# 20317.net
KiCad netlist of a schematic drawn in EAGLE
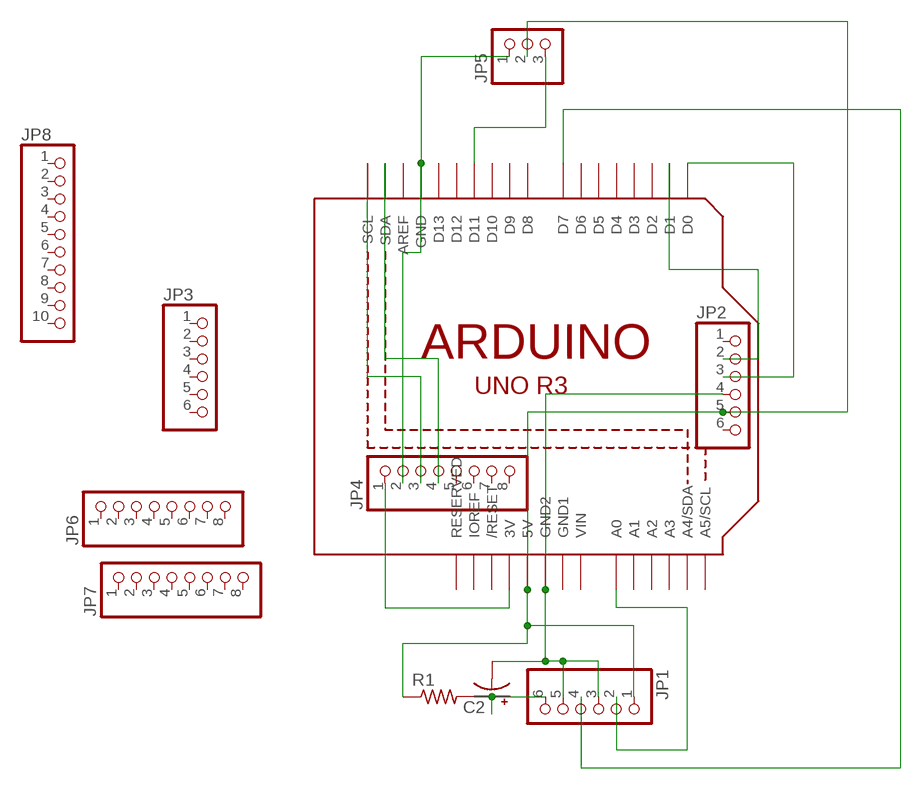
[diagram p0: schematic, sheet 1]

(export (version "E")
  (design (tool "Eeschema 10.0.6"))
  (components
    (comp (ref "C2")
      (value "CPOL-USE2.5-7")
      (footprint "eagle-import:E2,5-7")
      (libsource (lib "eagle-import") (part "CPOL-USE2.5-7"))
    )
    (comp (ref "JP1")
      (value "PINHD-1X6")
      (footprint "eagle-import:1X06")
      (libsource (lib "eagle-import") (part "PINHD-1X6"))
    )
    (comp (ref "JP2")
      (value "PINHD-1X6")
      (footprint "eagle-import:1X06")
      (libsource (lib "eagle-import") (part "PINHD-1X6"))
    )
    (comp (ref "JP3")
      (value "PINHD-1X6")
      (footprint "eagle-import:1X06")
      (libsource (lib "eagle-import") (part "PINHD-1X6"))
    )
    (comp (ref "JP4")
      (value "PINHD-1X8")
      (footprint "eagle-import:1X08")
      (libsource (lib "eagle-import") (part "PINHD-1X8"))
    )
    (comp (ref "JP5")
      (value "PINHD-1X3")
      (footprint "eagle-import:1X03")
      (libsource (lib "eagle-import") (part "PINHD-1X3"))
    )
    (comp (ref "JP6")
      (value "PINHD-1X8")
      (footprint "eagle-import:1X08")
      (libsource (lib "eagle-import") (part "PINHD-1X8"))
    )
    (comp (ref "JP7")
      (value "PINHD-1X8")
      (footprint "eagle-import:1X08")
      (libsource (lib "eagle-import") (part "PINHD-1X8"))
    )
    (comp (ref "JP8")
      (value "PINHD-1X10")
      (footprint "eagle-import:1X10")
      (libsource (lib "eagle-import") (part "PINHD-1X10"))
    )
    (comp (ref "R1")
      (value "R-US_0207/7")
      (footprint "eagle-import:0207_7")
      (libsource (lib "eagle-import") (part "R-US_0207/7"))
    )
    (comp (ref "U1")
      (value "ARDUINOR3-BPLACE")
      (footprint "eagle-import:ARDUINOR3-BPLACE")
      (libsource (lib "eagle-import") (part "ARDUINOR3-BPLACE"))
    )
  )
  (nets
    (net (code "1") (name "/GND1") (class "Default")
      (node (ref "U1") (pin "GND1") (pinfunction "GND1_GND1") (pintype "power_in"))
    )
    (net (code "2") (name "/VIN") (class "Default")
      (node (ref "U1") (pin "VIN") (pinfunction "VIN_VIN") (pintype "power_in"))
    )
    (net (code "3") (name "Net-(C2-Pad+)") (class "Default")
      (node (ref "C2") (pin "+") (pinfunction "+_+") (pintype "passive"))
      (node (ref "JP1") (pin "6") (pinfunction "6_6") (pintype "passive"))
      (node (ref "R1") (pin "2") (pinfunction "2_2") (pintype "passive"))
    )
    (net (code "4") (name "Net-(C2-Pad-)") (class "Default")
      (node (ref "C2") (pin "-") (pinfunction "-_-") (pintype "passive"))
      (node (ref "JP1") (pin "3") (pinfunction "3_3") (pintype "passive"))
      (node (ref "JP1") (pin "5") (pinfunction "5_5") (pintype "passive"))
      (node (ref "JP2") (pin "4") (pinfunction "4_4") (pintype "passive"))
      (node (ref "U1") (pin "GND2") (pinfunction "GND2_GND2") (pintype "power_in"))
    )
    (net (code "5") (name "Net-(JP1-Pad1)") (class "Default")
      (node (ref "JP1") (pin "1") (pinfunction "1_1") (pintype "passive"))
      (node (ref "JP2") (pin "5") (pinfunction "5_5") (pintype "passive"))
      (node (ref "JP5") (pin "2") (pinfunction "2_2") (pintype "passive"))
      (node (ref "R1") (pin "1") (pinfunction "1_1") (pintype "passive"))
      (node (ref "U1") (pin "5V") (pinfunction "5V_5V") (pintype "power_in"))
    )
    (net (code "6") (name "Net-(JP1-Pad2)") (class "Default")
      (node (ref "JP1") (pin "2") (pinfunction "2_2") (pintype "passive"))
      (node (ref "U1") (pin "A0") (pinfunction "A0_A0") (pintype "bidirectional"))
    )
    (net (code "7") (name "Net-(JP1-Pad4)") (class "Default")
      (node (ref "JP1") (pin "4") (pinfunction "4_4") (pintype "passive"))
      (node (ref "U1") (pin "D7") (pinfunction "D7_D7") (pintype "bidirectional"))
    )
    (net (code "8") (name "Net-(JP2-Pad2)") (class "Default")
      (node (ref "JP2") (pin "2") (pinfunction "2_2") (pintype "passive"))
      (node (ref "U1") (pin "D1") (pinfunction "D1_D1") (pintype "bidirectional"))
    )
    (net (code "9") (name "Net-(JP2-Pad3)") (class "Default")
      (node (ref "JP2") (pin "3") (pinfunction "3_3") (pintype "passive"))
      (node (ref "U1") (pin "D0") (pinfunction "D0_D0") (pintype "bidirectional"))
    )
    (net (code "10") (name "Net-(JP4-Pad1)") (class "Default")
      (node (ref "JP4") (pin "1") (pinfunction "1_1") (pintype "passive"))
      (node (ref "U1") (pin "3V") (pinfunction "3V_3V") (pintype "power_in"))
    )
    (net (code "11") (name "Net-(JP4-Pad2)") (class "Default")
      (node (ref "JP4") (pin "2") (pinfunction "2_2") (pintype "passive"))
      (node (ref "JP5") (pin "1") (pinfunction "1_1") (pintype "passive"))
      (node (ref "U1") (pin "GND") (pinfunction "GND_GND") (pintype "power_in"))
    )
    (net (code "12") (name "Net-(JP4-Pad3)") (class "Default")
      (node (ref "JP4") (pin "3") (pinfunction "3_3") (pintype "passive"))
      (node (ref "U1") (pin "SCL") (pinfunction "SCL_SCL") (pintype "bidirectional"))
    )
    (net (code "13") (name "Net-(JP4-Pad4)") (class "Default")
      (node (ref "JP4") (pin "4") (pinfunction "4_4") (pintype "passive"))
      (node (ref "U1") (pin "SDA") (pinfunction "SDA_SDA") (pintype "bidirectional"))
    )
    (net (code "14") (name "Net-(JP5-Pad3)") (class "Default")
      (node (ref "JP5") (pin "3") (pinfunction "3_3") (pintype "passive"))
      (node (ref "U1") (pin "D11") (pinfunction "D11_D11") (pintype "bidirectional"))
    )
    (net (code "15") (name "unconnected-(JP2-Pad1)") (class "Default")
      (node (ref "JP2") (pin "1") (pinfunction "1_1") (pintype "passive"))
    )
    (net (code "16") (name "unconnected-(JP2-Pad6)") (class "Default")
      (node (ref "JP2") (pin "6") (pinfunction "6_6") (pintype "passive"))
    )
    (net (code "17") (name "unconnected-(JP3-Pad1)") (class "Default")
      (node (ref "JP3") (pin "1") (pinfunction "1_1") (pintype "passive"))
    )
    (net (code "18") (name "unconnected-(JP3-Pad2)") (class "Default")
      (node (ref "JP3") (pin "2") (pinfunction "2_2") (pintype "passive"))
    )
    (net (code "19") (name "unconnected-(JP3-Pad3)") (class "Default")
      (node (ref "JP3") (pin "3") (pinfunction "3_3") (pintype "passive"))
    )
    (net (code "20") (name "unconnected-(JP3-Pad4)") (class "Default")
      (node (ref "JP3") (pin "4") (pinfunction "4_4") (pintype "passive"))
    )
    (net (code "21") (name "unconnected-(JP3-Pad5)") (class "Default")
      (node (ref "JP3") (pin "5") (pinfunction "5_5") (pintype "passive"))
    )
    (net (code "22") (name "unconnected-(JP3-Pad6)") (class "Default")
      (node (ref "JP3") (pin "6") (pinfunction "6_6") (pintype "passive"))
    )
    (net (code "23") (name "unconnected-(JP4-Pad5)") (class "Default")
      (node (ref "JP4") (pin "5") (pinfunction "5_5") (pintype "passive"))
    )
    (net (code "24") (name "unconnected-(JP4-Pad6)") (class "Default")
      (node (ref "JP4") (pin "6") (pinfunction "6_6") (pintype "passive"))
    )
    (net (code "25") (name "unconnected-(JP4-Pad7)") (class "Default")
      (node (ref "JP4") (pin "7") (pinfunction "7_7") (pintype "passive"))
    )
    (net (code "26") (name "unconnected-(JP4-Pad8)") (class "Default")
      (node (ref "JP4") (pin "8") (pinfunction "8_8") (pintype "passive"))
    )
    (net (code "27") (name "unconnected-(JP6-Pad1)") (class "Default")
      (node (ref "JP6") (pin "1") (pinfunction "1_1") (pintype "passive"))
    )
    (net (code "28") (name "unconnected-(JP6-Pad2)") (class "Default")
      (node (ref "JP6") (pin "2") (pinfunction "2_2") (pintype "passive"))
    )
    (net (code "29") (name "unconnected-(JP6-Pad3)") (class "Default")
      (node (ref "JP6") (pin "3") (pinfunction "3_3") (pintype "passive"))
    )
    (net (code "30") (name "unconnected-(JP6-Pad4)") (class "Default")
      (node (ref "JP6") (pin "4") (pinfunction "4_4") (pintype "passive"))
    )
    (net (code "31") (name "unconnected-(JP6-Pad5)") (class "Default")
      (node (ref "JP6") (pin "5") (pinfunction "5_5") (pintype "passive"))
    )
    (net (code "32") (name "unconnected-(JP6-Pad6)") (class "Default")
      (node (ref "JP6") (pin "6") (pinfunction "6_6") (pintype "passive"))
    )
    (net (code "33") (name "unconnected-(JP6-Pad7)") (class "Default")
      (node (ref "JP6") (pin "7") (pinfunction "7_7") (pintype "passive"))
    )
    (net (code "34") (name "unconnected-(JP6-Pad8)") (class "Default")
      (node (ref "JP6") (pin "8") (pinfunction "8_8") (pintype "passive"))
    )
    (net (code "35") (name "unconnected-(JP7-Pad1)") (class "Default")
      (node (ref "JP7") (pin "1") (pinfunction "1_1") (pintype "passive"))
    )
    (net (code "36") (name "unconnected-(JP7-Pad2)") (class "Default")
      (node (ref "JP7") (pin "2") (pinfunction "2_2") (pintype "passive"))
    )
    (net (code "37") (name "unconnected-(JP7-Pad3)") (class "Default")
      (node (ref "JP7") (pin "3") (pinfunction "3_3") (pintype "passive"))
    )
    (net (code "38") (name "unconnected-(JP7-Pad4)") (class "Default")
      (node (ref "JP7") (pin "4") (pinfunction "4_4") (pintype "passive"))
    )
    (net (code "39") (name "unconnected-(JP7-Pad5)") (class "Default")
      (node (ref "JP7") (pin "5") (pinfunction "5_5") (pintype "passive"))
    )
    (net (code "40") (name "unconnected-(JP7-Pad6)") (class "Default")
      (node (ref "JP7") (pin "6") (pinfunction "6_6") (pintype "passive"))
    )
    (net (code "41") (name "unconnected-(JP7-Pad7)") (class "Default")
      (node (ref "JP7") (pin "7") (pinfunction "7_7") (pintype "passive"))
    )
    (net (code "42") (name "unconnected-(JP7-Pad8)") (class "Default")
      (node (ref "JP7") (pin "8") (pinfunction "8_8") (pintype "passive"))
    )
    (net (code "43") (name "unconnected-(JP8-Pad1)") (class "Default")
      (node (ref "JP8") (pin "1") (pinfunction "1_1") (pintype "passive"))
    )
    (net (code "44") (name "unconnected-(JP8-Pad2)") (class "Default")
      (node (ref "JP8") (pin "2") (pinfunction "2_2") (pintype "passive"))
    )
    (net (code "45") (name "unconnected-(JP8-Pad3)") (class "Default")
      (node (ref "JP8") (pin "3") (pinfunction "3_3") (pintype "passive"))
    )
    (net (code "46") (name "unconnected-(JP8-Pad4)") (class "Default")
      (node (ref "JP8") (pin "4") (pinfunction "4_4") (pintype "passive"))
    )
    (net (code "47") (name "unconnected-(JP8-Pad5)") (class "Default")
      (node (ref "JP8") (pin "5") (pinfunction "5_5") (pintype "passive"))
    )
    (net (code "48") (name "unconnected-(JP8-Pad6)") (class "Default")
      (node (ref "JP8") (pin "6") (pinfunction "6_6") (pintype "passive"))
    )
    (net (code "49") (name "unconnected-(JP8-Pad7)") (class "Default")
      (node (ref "JP8") (pin "7") (pinfunction "7_7") (pintype "passive"))
    )
    (net (code "50") (name "unconnected-(JP8-Pad8)") (class "Default")
      (node (ref "JP8") (pin "8") (pinfunction "8_8") (pintype "passive"))
    )
    (net (code "51") (name "unconnected-(JP8-Pad9)") (class "Default")
      (node (ref "JP8") (pin "9") (pinfunction "9_9") (pintype "passive"))
    )
    (net (code "52") (name "unconnected-(JP8-Pad10)") (class "Default")
      (node (ref "JP8") (pin "10") (pinfunction "10_10") (pintype "passive"))
    )
    (net (code "53") (name "unconnected-(U1-A4{slash}SDA-PadA4)") (class "Default")
      (node (ref "U1") (pin "A4") (pinfunction "A4/SDA_A4") (pintype "bidirectional"))
    )
    (net (code "54") (name "unconnected-(U1-A5{slash}SCL-PadA5)") (class "Default")
      (node (ref "U1") (pin "A5") (pinfunction "A5/SCL_A5") (pintype "bidirectional"))
    )
    (net (code "55") (name "unconnected-(U1-PadA1)") (class "Default")
      (node (ref "U1") (pin "A1") (pinfunction "A1_A1") (pintype "bidirectional"))
    )
    (net (code "56") (name "unconnected-(U1-PadA2)") (class "Default")
      (node (ref "U1") (pin "A2") (pinfunction "A2_A2") (pintype "bidirectional"))
    )
    (net (code "57") (name "unconnected-(U1-PadA3)") (class "Default")
      (node (ref "U1") (pin "A3") (pinfunction "A3_A3") (pintype "bidirectional"))
    )
    (net (code "58") (name "unconnected-(U1-PadAREF)") (class "Default")
      (node (ref "U1") (pin "AREF") (pinfunction "AREF_AREF") (pintype "bidirectional"))
    )
    (net (code "59") (name "unconnected-(U1-PadD2)") (class "Default")
      (node (ref "U1") (pin "D2") (pinfunction "D2_D2") (pintype "bidirectional"))
    )
    (net (code "60") (name "unconnected-(U1-PadD3)") (class "Default")
      (node (ref "U1") (pin "D3") (pinfunction "D3_D3") (pintype "bidirectional"))
    )
    (net (code "61") (name "unconnected-(U1-PadD4)") (class "Default")
      (node (ref "U1") (pin "D4") (pinfunction "D4_D4") (pintype "bidirectional"))
    )
    (net (code "62") (name "unconnected-(U1-PadD5)") (class "Default")
      (node (ref "U1") (pin "D5") (pinfunction "D5_D5") (pintype "bidirectional"))
    )
    (net (code "63") (name "unconnected-(U1-PadD6)") (class "Default")
      (node (ref "U1") (pin "D6") (pinfunction "D6_D6") (pintype "bidirectional"))
    )
    (net (code "64") (name "unconnected-(U1-PadD8)") (class "Default")
      (node (ref "U1") (pin "D8") (pinfunction "D8_D8") (pintype "bidirectional"))
    )
    (net (code "65") (name "unconnected-(U1-PadD9)") (class "Default")
      (node (ref "U1") (pin "D9") (pinfunction "D9_D9") (pintype "bidirectional"))
    )
    (net (code "66") (name "unconnected-(U1-PadD10)") (class "Default")
      (node (ref "U1") (pin "D10") (pinfunction "D10_D10") (pintype "bidirectional"))
    )
    (net (code "67") (name "unconnected-(U1-PadD12)") (class "Default")
      (node (ref "U1") (pin "D12") (pinfunction "D12_D12") (pintype "bidirectional"))
    )
    (net (code "68") (name "unconnected-(U1-PadD13)") (class "Default")
      (node (ref "U1") (pin "D13") (pinfunction "D13_D13") (pintype "bidirectional"))
    )
    (net (code "69") (name "unconnected-(U1-PadIOREF)") (class "Default")
      (node (ref "U1") (pin "IOREF") (pinfunction "IOREF_IOREF") (pintype "output"))
    )
    (net (code "70") (name "unconnected-(U1-PadRESERVED)") (class "Default")
      (node (ref "U1") (pin "RESERVED") (pinfunction "RESERVED_RESERVED") (pintype "no_connect"))
    )
    (net (code "71") (name "unconnected-(U1-{slash}RESET-PadRESET)") (class "Default")
      (node (ref "U1") (pin "RESET") (pinfunction "/RESET_RESET") (pintype "bidirectional"))
    )
  )
)
